# FPGA_board_and_power.net
KiCad netlist of a schematic drawn in Altium Designer
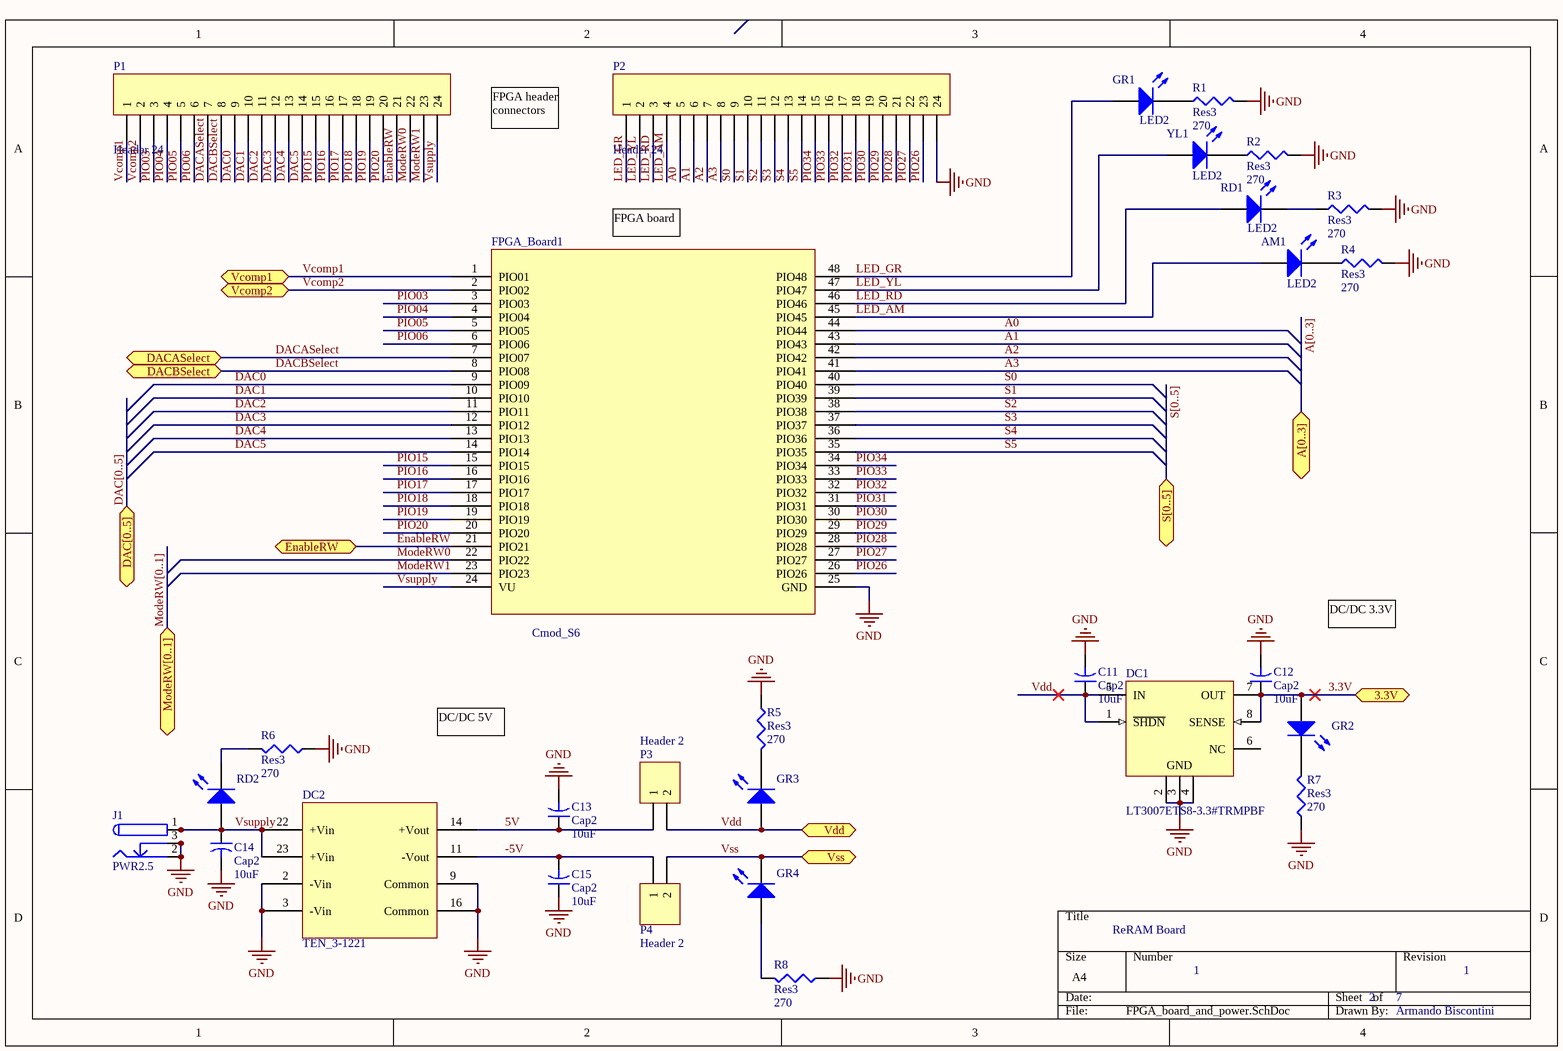
[diagram p0: FPGA_board_and_power.SchDoc]

(export (version "E")
  (design (tool "Eeschema 10.0.6"))
  (components
    (comp (ref "AM1")
      (value "LED2")
      (footprint "3.2X1.6X1.1")
      (description "Typical RED, GREEN, YELLOW, AMBER GaAs LED")
      (fields (field (name "PUBLISHER") "Altium Limited"))
      (libsource (lib "Miscellaneous Devices") (part "LED2"))
    )
    (comp (ref "C11")
      (value "Cap2")
      (footprint "CAPR5-4X5")
      (description "Capacitor")
      (fields (field (name "ALTIUM_VALUE") "10uF") (field (name "PUBLISHER") "Altium Limited"))
      (libsource (lib "Miscellaneous Devices") (part "Cap2"))
    )
    (comp (ref "C12")
      (value "Cap2")
      (footprint "CAPR5-4X5")
      (description "Capacitor")
      (fields (field (name "ALTIUM_VALUE") "10uF") (field (name "PUBLISHER") "Altium Limited"))
      (libsource (lib "Miscellaneous Devices") (part "Cap2"))
    )
    (comp (ref "C13")
      (value "Cap2")
      (footprint "CAPR5-4X5")
      (description "Capacitor")
      (fields (field (name "ALTIUM_VALUE") "10uF") (field (name "PUBLISHER") "Altium Limited"))
      (libsource (lib "Miscellaneous Devices") (part "Cap2"))
    )
    (comp (ref "C14")
      (value "Cap2")
      (footprint "CAPR5-4X5")
      (description "Capacitor")
      (fields (field (name "ALTIUM_VALUE") "10uF") (field (name "PUBLISHER") "Altium Limited"))
      (libsource (lib "Miscellaneous Devices") (part "Cap2"))
    )
    (comp (ref "C15")
      (value "Cap2")
      (footprint "CAPR5-4X5")
      (description "Capacitor")
      (fields (field (name "ALTIUM_VALUE") "10uF") (field (name "PUBLISHER") "Altium Limited"))
      (libsource (lib "Miscellaneous Devices") (part "Cap2"))
    )
    (comp (ref "DC1")
      (value "LT3007ETS8-3.3#TRMPBF")
      (footprint "LT-TS8-8-TSOT-23_V")
      (fields (field (name "MANUFACTURER") "Linear Technology"))
      (libsource (lib "Linear Technology Power Management LDO Linear Regulators") (part "LT3007ETS8-3.3#TRMPBF"))
    )
    (comp (ref "DC2")
      (value "TEN_3-1221")
      (footprint "TEN_3-1221")
      (description "Tracopower TEN 3-1221")
      (libsource (lib "ReRAM_Board_library") (part "TEN_3-1221"))
    )
    (comp (ref "FPGA_Board1")
      (value "Cmod_S6")
      (footprint "Cmod_S6_double_conn")
      (description "Digilent Cmod S6 Board")
      (libsource (lib "ReRAM_Board_library") (part "Cmod_S6"))
    )
    (comp (ref "GR1")
      (value "LED2")
      (footprint "3.2X1.6X1.1")
      (description "Typical RED, GREEN, YELLOW, AMBER GaAs LED")
      (fields (field (name "PUBLISHER") "Altium Limited"))
      (libsource (lib "Miscellaneous Devices") (part "LED2"))
    )
    (comp (ref "GR2")
      (value "~")
      (footprint "3.2X1.6X1.1")
      (description "Typical RED, GREEN, YELLOW, AMBER GaAs LED")
      (fields (field (name "PUBLISHER") "Altium Limited"))
      (libsource (lib "Miscellaneous Devices") (part "LED2"))
    )
    (comp (ref "GR3")
      (value "~")
      (footprint "3.2X1.6X1.1")
      (description "Typical RED, GREEN, YELLOW, AMBER GaAs LED")
      (fields (field (name "PUBLISHER") "Altium Limited"))
      (libsource (lib "Miscellaneous Devices") (part "LED2"))
    )
    (comp (ref "GR4")
      (value "~")
      (footprint "3.2X1.6X1.1")
      (description "Typical RED, GREEN, YELLOW, AMBER GaAs LED")
      (fields (field (name "PUBLISHER") "Altium Limited"))
      (libsource (lib "Miscellaneous Devices") (part "LED2"))
    )
    (comp (ref "J1")
      (value "PWR2.5")
      (footprint "KLD-0202")
      (description "Low Voltage Power Supply Connector")
      (fields (field (name "PUBLISHER") "Altium Limited"))
      (libsource (lib "Miscellaneous Connectors") (part "PWR2.5"))
    )
    (comp (ref "P1")
      (value "Header 24")
      (footprint "HDR1X24")
      (description "Header, 24-Pin")
      (fields (field (name "PUBLISHER") "Altium Limited"))
      (libsource (lib "Miscellaneous Connectors") (part "Header 24"))
    )
    (comp (ref "P2")
      (value "Header 24")
      (footprint "HDR1X24")
      (description "Header, 24-Pin")
      (fields (field (name "PUBLISHER") "Altium Limited"))
      (libsource (lib "Miscellaneous Connectors") (part "Header 24"))
    )
    (comp (ref "P3")
      (value "Header 2")
      (footprint "HDR1X2")
      (description "Header, 2-Pin")
      (fields (field (name "PUBLISHER") "Altium Limited"))
      (libsource (lib "") (part "Header 2_1"))
    )
    (comp (ref "P4")
      (value "Header 2")
      (footprint "HDR1X2")
      (description "Header, 2-Pin")
      (fields (field (name "PUBLISHER") "Altium Limited"))
      (libsource (lib "Miscellaneous Connectors") (part "Header 2"))
    )
    (comp (ref "R1")
      (value "Res3")
      (footprint "J1-0603")
      (description "Resistor")
      (fields (field (name "ALTIUM_VALUE") "270") (field (name "PUBLISHER") "Altium Limited"))
      (libsource (lib "Miscellaneous Devices") (part "Res3"))
    )
    (comp (ref "R2")
      (value "Res3")
      (footprint "J1-0603")
      (description "Resistor")
      (fields (field (name "ALTIUM_VALUE") "270") (field (name "PUBLISHER") "Altium Limited"))
      (libsource (lib "Miscellaneous Devices") (part "Res3"))
    )
    (comp (ref "R3")
      (value "Res3")
      (footprint "J1-0603")
      (description "Resistor")
      (fields (field (name "ALTIUM_VALUE") "270") (field (name "PUBLISHER") "Altium Limited"))
      (libsource (lib "Miscellaneous Devices") (part "Res3"))
    )
    (comp (ref "R4")
      (value "Res3")
      (footprint "J1-0603")
      (description "Resistor")
      (fields (field (name "ALTIUM_VALUE") "270") (field (name "PUBLISHER") "Altium Limited"))
      (libsource (lib "Miscellaneous Devices") (part "Res3"))
    )
    (comp (ref "R5")
      (value "Res3")
      (footprint "J1-0603")
      (description "Resistor")
      (fields (field (name "ALTIUM_VALUE") "270") (field (name "PUBLISHER") "Altium Limited"))
      (libsource (lib "Miscellaneous Devices") (part "Res3"))
    )
    (comp (ref "R6")
      (value "Res3")
      (footprint "J1-0603")
      (description "Resistor")
      (fields (field (name "ALTIUM_VALUE") "270") (field (name "PUBLISHER") "Altium Limited"))
      (libsource (lib "Miscellaneous Devices") (part "Res3"))
    )
    (comp (ref "R7")
      (value "Res3")
      (footprint "J1-0603")
      (description "Resistor")
      (fields (field (name "ALTIUM_VALUE") "270") (field (name "PUBLISHER") "Altium Limited"))
      (libsource (lib "Miscellaneous Devices") (part "Res3"))
    )
    (comp (ref "R8")
      (value "Res3")
      (footprint "J1-0603")
      (description "Resistor")
      (fields (field (name "ALTIUM_VALUE") "270") (field (name "PUBLISHER") "Altium Limited"))
      (libsource (lib "Miscellaneous Devices") (part "Res3"))
    )
    (comp (ref "RD1")
      (value "LED2")
      (footprint "3.2X1.6X1.1")
      (description "Typical RED, GREEN, YELLOW, AMBER GaAs LED")
      (fields (field (name "PUBLISHER") "Altium Limited"))
      (libsource (lib "Miscellaneous Devices") (part "LED2"))
    )
    (comp (ref "RD2")
      (value "~")
      (footprint "3.2X1.6X1.1")
      (description "Typical RED, GREEN, YELLOW, AMBER GaAs LED")
      (fields (field (name "PUBLISHER") "Altium Limited"))
      (libsource (lib "Miscellaneous Devices") (part "LED2"))
    )
    (comp (ref "YL1")
      (value "LED2")
      (footprint "3.2X1.6X1.1")
      (description "Typical RED, GREEN, YELLOW, AMBER GaAs LED")
      (fields (field (name "PUBLISHER") "Altium Limited"))
      (libsource (lib "Miscellaneous Devices") (part "LED2"))
    )
  )
  (nets
    (net (code "1") (name "/-5V") (class "Default")
      (node (ref "C15") (pin "2") (pinfunction "2_2") (pintype "passive"))
      (node (ref "DC2") (pin "11") (pinfunction "-Vout_11") (pintype "passive"))
      (node (ref "P4") (pin "1") (pinfunction "1_1") (pintype "passive"))
    )
    (net (code "2") (name "/3.3V") (class "Default")
      (node (ref "C12") (pin "1") (pinfunction "1_1") (pintype "passive"))
      (node (ref "DC1") (pin "7") (pinfunction "OUT_7") (pintype "power_in"))
      (node (ref "DC1") (pin "8") (pinfunction "SENSE_8") (pintype "input"))
      (node (ref "GR2") (pin "1") (pinfunction "A_1") (pintype "passive"))
    )
    (net (code "3") (name "/5V") (class "Default")
      (node (ref "C13") (pin "1") (pinfunction "1_1") (pintype "passive"))
      (node (ref "DC2") (pin "14") (pinfunction "+Vout_14") (pintype "passive"))
      (node (ref "P3") (pin "1") (pinfunction "1_1") (pintype "passive"))
    )
    (net (code "4") (name "/A0") (class "Default")
      (node (ref "FPGA_Board1") (pin "44") (pinfunction "PIO44_44") (pintype "passive"))
      (node (ref "P2") (pin "5") (pinfunction "5_5") (pintype "passive"))
    )
    (net (code "5") (name "/A1") (class "Default")
      (node (ref "FPGA_Board1") (pin "43") (pinfunction "PIO43_43") (pintype "passive"))
      (node (ref "P2") (pin "6") (pinfunction "6_6") (pintype "passive"))
    )
    (net (code "6") (name "/A2") (class "Default")
      (node (ref "FPGA_Board1") (pin "42") (pinfunction "PIO42_42") (pintype "passive"))
      (node (ref "P2") (pin "7") (pinfunction "7_7") (pintype "passive"))
    )
    (net (code "7") (name "/A3") (class "Default")
      (node (ref "FPGA_Board1") (pin "41") (pinfunction "PIO41_41") (pintype "passive"))
      (node (ref "P2") (pin "8") (pinfunction "8_8") (pintype "passive"))
    )
    (net (code "9") (name "/DAC0") (class "Default")
      (node (ref "FPGA_Board1") (pin "9") (pinfunction "PIO09_9") (pintype "passive"))
      (node (ref "P1") (pin "9") (pinfunction "9_9") (pintype "passive"))
    )
    (net (code "10") (name "/DAC1") (class "Default")
      (node (ref "FPGA_Board1") (pin "10") (pinfunction "PIO10_10") (pintype "passive"))
      (node (ref "P1") (pin "10") (pinfunction "10_10") (pintype "passive"))
    )
    (net (code "11") (name "/DAC2") (class "Default")
      (node (ref "FPGA_Board1") (pin "11") (pinfunction "PIO11_11") (pintype "passive"))
      (node (ref "P1") (pin "11") (pinfunction "11_11") (pintype "passive"))
    )
    (net (code "12") (name "/DAC3") (class "Default")
      (node (ref "FPGA_Board1") (pin "12") (pinfunction "PIO12_12") (pintype "passive"))
      (node (ref "P1") (pin "12") (pinfunction "12_12") (pintype "passive"))
    )
    (net (code "13") (name "/DAC4") (class "Default")
      (node (ref "FPGA_Board1") (pin "13") (pinfunction "PIO13_13") (pintype "passive"))
      (node (ref "P1") (pin "13") (pinfunction "13_13") (pintype "passive"))
    )
    (net (code "14") (name "/DAC5") (class "Default")
      (node (ref "FPGA_Board1") (pin "14") (pinfunction "PIO14_14") (pintype "passive"))
      (node (ref "P1") (pin "14") (pinfunction "14_14") (pintype "passive"))
    )
    (net (code "15") (name "/DACASelect") (class "Default")
      (node (ref "FPGA_Board1") (pin "7") (pinfunction "PIO07_7") (pintype "passive"))
      (node (ref "P1") (pin "7") (pinfunction "7_7") (pintype "passive"))
    )
    (net (code "16") (name "/DACBSelect") (class "Default")
      (node (ref "FPGA_Board1") (pin "8") (pinfunction "PIO08_8") (pintype "passive"))
      (node (ref "P1") (pin "8") (pinfunction "8_8") (pintype "passive"))
    )
    (net (code "18") (name "/EnableRW") (class "Default")
      (node (ref "FPGA_Board1") (pin "21") (pinfunction "PIO21_21") (pintype "passive"))
      (node (ref "P1") (pin "21") (pinfunction "21_21") (pintype "passive"))
    )
    (net (code "19") (name "/LED_AM") (class "Default")
      (node (ref "AM1") (pin "1") (pinfunction "A_1") (pintype "passive"))
      (node (ref "FPGA_Board1") (pin "45") (pinfunction "PIO45_45") (pintype "passive"))
      (node (ref "P2") (pin "4") (pinfunction "4_4") (pintype "passive"))
    )
    (net (code "20") (name "/LED_GR") (class "Default")
      (node (ref "FPGA_Board1") (pin "48") (pinfunction "PIO48_48") (pintype "passive"))
      (node (ref "GR1") (pin "1") (pinfunction "A_1") (pintype "passive"))
      (node (ref "P2") (pin "1") (pinfunction "1_1") (pintype "passive"))
    )
    (net (code "21") (name "/LED_RD") (class "Default")
      (node (ref "FPGA_Board1") (pin "46") (pinfunction "PIO46_46") (pintype "passive"))
      (node (ref "P2") (pin "3") (pinfunction "3_3") (pintype "passive"))
      (node (ref "RD1") (pin "1") (pinfunction "A_1") (pintype "passive"))
    )
    (net (code "22") (name "/LED_YL") (class "Default")
      (node (ref "FPGA_Board1") (pin "47") (pinfunction "PIO47_47") (pintype "passive"))
      (node (ref "P2") (pin "2") (pinfunction "2_2") (pintype "passive"))
      (node (ref "YL1") (pin "1") (pinfunction "A_1") (pintype "passive"))
    )
    (net (code "23") (name "/ModeRW0") (class "Default")
      (node (ref "FPGA_Board1") (pin "22") (pinfunction "PIO22_22") (pintype "passive"))
      (node (ref "P1") (pin "22") (pinfunction "22_22") (pintype "passive"))
    )
    (net (code "24") (name "/ModeRW1") (class "Default")
      (node (ref "FPGA_Board1") (pin "23") (pinfunction "PIO23_23") (pintype "passive"))
      (node (ref "P1") (pin "23") (pinfunction "23_23") (pintype "passive"))
    )
    (net (code "26") (name "/PIO03") (class "Default")
      (node (ref "FPGA_Board1") (pin "3") (pinfunction "PIO03_3") (pintype "passive"))
      (node (ref "P1") (pin "3") (pinfunction "3_3") (pintype "passive"))
    )
    (net (code "27") (name "/PIO04") (class "Default")
      (node (ref "FPGA_Board1") (pin "4") (pinfunction "PIO04_4") (pintype "passive"))
      (node (ref "P1") (pin "4") (pinfunction "4_4") (pintype "passive"))
    )
    (net (code "28") (name "/PIO05") (class "Default")
      (node (ref "FPGA_Board1") (pin "5") (pinfunction "PIO05_5") (pintype "passive"))
      (node (ref "P1") (pin "5") (pinfunction "5_5") (pintype "passive"))
    )
    (net (code "29") (name "/PIO06") (class "Default")
      (node (ref "FPGA_Board1") (pin "6") (pinfunction "PIO06_6") (pintype "passive"))
      (node (ref "P1") (pin "6") (pinfunction "6_6") (pintype "passive"))
    )
    (net (code "30") (name "/PIO15") (class "Default")
      (node (ref "FPGA_Board1") (pin "15") (pinfunction "PIO15_15") (pintype "passive"))
      (node (ref "P1") (pin "15") (pinfunction "15_15") (pintype "passive"))
    )
    (net (code "31") (name "/PIO16") (class "Default")
      (node (ref "FPGA_Board1") (pin "16") (pinfunction "PIO16_16") (pintype "passive"))
      (node (ref "P1") (pin "16") (pinfunction "16_16") (pintype "passive"))
    )
    (net (code "32") (name "/PIO17") (class "Default")
      (node (ref "FPGA_Board1") (pin "17") (pinfunction "PIO17_17") (pintype "passive"))
      (node (ref "P1") (pin "17") (pinfunction "17_17") (pintype "passive"))
    )
    (net (code "33") (name "/PIO18") (class "Default")
      (node (ref "FPGA_Board1") (pin "18") (pinfunction "PIO18_18") (pintype "passive"))
      (node (ref "P1") (pin "18") (pinfunction "18_18") (pintype "passive"))
    )
    (net (code "34") (name "/PIO19") (class "Default")
      (node (ref "FPGA_Board1") (pin "19") (pinfunction "PIO19_19") (pintype "passive"))
      (node (ref "P1") (pin "19") (pinfunction "19_19") (pintype "passive"))
    )
    (net (code "35") (name "/PIO20") (class "Default")
      (node (ref "FPGA_Board1") (pin "20") (pinfunction "PIO20_20") (pintype "passive"))
      (node (ref "P1") (pin "20") (pinfunction "20_20") (pintype "passive"))
    )
    (net (code "36") (name "/PIO26") (class "Default")
      (node (ref "FPGA_Board1") (pin "26") (pinfunction "PIO26_26") (pintype "passive"))
      (node (ref "P2") (pin "23") (pinfunction "23_23") (pintype "passive"))
    )
    (net (code "37") (name "/PIO27") (class "Default")
      (node (ref "FPGA_Board1") (pin "27") (pinfunction "PIO27_27") (pintype "passive"))
      (node (ref "P2") (pin "22") (pinfunction "22_22") (pintype "passive"))
    )
    (net (code "38") (name "/PIO28") (class "Default")
      (node (ref "FPGA_Board1") (pin "28") (pinfunction "PIO28_28") (pintype "passive"))
      (node (ref "P2") (pin "21") (pinfunction "21_21") (pintype "passive"))
    )
    (net (code "39") (name "/PIO29") (class "Default")
      (node (ref "FPGA_Board1") (pin "29") (pinfunction "PIO29_29") (pintype "passive"))
      (node (ref "P2") (pin "20") (pinfunction "20_20") (pintype "passive"))
    )
    (net (code "40") (name "/PIO30") (class "Default")
      (node (ref "FPGA_Board1") (pin "30") (pinfunction "PIO30_30") (pintype "passive"))
      (node (ref "P2") (pin "19") (pinfunction "19_19") (pintype "passive"))
    )
    (net (code "41") (name "/PIO31") (class "Default")
      (node (ref "FPGA_Board1") (pin "31") (pinfunction "PIO31_31") (pintype "passive"))
      (node (ref "P2") (pin "18") (pinfunction "18_18") (pintype "passive"))
    )
    (net (code "42") (name "/PIO32") (class "Default")
      (node (ref "FPGA_Board1") (pin "32") (pinfunction "PIO32_32") (pintype "passive"))
      (node (ref "P2") (pin "17") (pinfunction "17_17") (pintype "passive"))
    )
    (net (code "43") (name "/PIO33") (class "Default")
      (node (ref "FPGA_Board1") (pin "33") (pinfunction "PIO33_33") (pintype "passive"))
      (node (ref "P2") (pin "16") (pinfunction "16_16") (pintype "passive"))
    )
    (net (code "44") (name "/PIO34") (class "Default")
      (node (ref "FPGA_Board1") (pin "34") (pinfunction "PIO34_34") (pintype "passive"))
      (node (ref "P2") (pin "15") (pinfunction "15_15") (pintype "passive"))
    )
    (net (code "45") (name "/S0") (class "Default")
      (node (ref "FPGA_Board1") (pin "40") (pinfunction "PIO40_40") (pintype "passive"))
      (node (ref "P2") (pin "9") (pinfunction "9_9") (pintype "passive"))
    )
    (net (code "46") (name "/S1") (class "Default")
      (node (ref "FPGA_Board1") (pin "39") (pinfunction "PIO39_39") (pintype "passive"))
      (node (ref "P2") (pin "10") (pinfunction "10_10") (pintype "passive"))
    )
    (net (code "47") (name "/S2") (class "Default")
      (node (ref "FPGA_Board1") (pin "38") (pinfunction "PIO38_38") (pintype "passive"))
      (node (ref "P2") (pin "11") (pinfunction "11_11") (pintype "passive"))
    )
    (net (code "48") (name "/S3") (class "Default")
      (node (ref "FPGA_Board1") (pin "37") (pinfunction "PIO37_37") (pintype "passive"))
      (node (ref "P2") (pin "12") (pinfunction "12_12") (pintype "passive"))
    )
    (net (code "49") (name "/S4") (class "Default")
      (node (ref "FPGA_Board1") (pin "36") (pinfunction "PIO36_36") (pintype "passive"))
      (node (ref "P2") (pin "13") (pinfunction "13_13") (pintype "passive"))
    )
    (net (code "50") (name "/S5") (class "Default")
      (node (ref "FPGA_Board1") (pin "35") (pinfunction "PIO35_35") (pintype "passive"))
      (node (ref "P2") (pin "14") (pinfunction "14_14") (pintype "passive"))
    )
    (net (code "52") (name "/Vcomp1") (class "Default")
      (node (ref "FPGA_Board1") (pin "1") (pinfunction "PIO01_1") (pintype "passive"))
      (node (ref "P1") (pin "1") (pinfunction "1_1") (pintype "passive"))
    )
    (net (code "53") (name "/Vcomp2") (class "Default")
      (node (ref "FPGA_Board1") (pin "2") (pinfunction "PIO02_2") (pintype "passive"))
      (node (ref "P1") (pin "2") (pinfunction "2_2") (pintype "passive"))
    )
    (net (code "54") (name "/Vdd") (class "Default")
      (node (ref "C11") (pin "1") (pinfunction "1_1") (pintype "passive"))
      (node (ref "DC1") (pin "1") (pinfunction "~{SHDN}_1") (pintype "input"))
      (node (ref "DC1") (pin "5") (pinfunction "IN_5") (pintype "power_in"))
      (node (ref "GR3") (pin "1") (pinfunction "A_1") (pintype "passive"))
      (node (ref "P3") (pin "2") (pinfunction "2_2") (pintype "passive"))
    )
    (net (code "55") (name "/Vss") (class "Default")
      (node (ref "GR4") (pin "2") (pinfunction "K_2") (pintype "passive"))
      (node (ref "P4") (pin "2") (pinfunction "2_2") (pintype "passive"))
    )
    (net (code "56") (name "/Vsupply") (class "Default")
      (node (ref "C14") (pin "1") (pinfunction "1_1") (pintype "passive"))
      (node (ref "DC2") (pin "22") (pinfunction "+Vin_22") (pintype "passive"))
      (node (ref "DC2") (pin "23") (pinfunction "+Vin_23") (pintype "passive"))
      (node (ref "FPGA_Board1") (pin "24") (pinfunction "VU_24") (pintype "passive"))
      (node (ref "J1") (pin "1") (pinfunction "1_1") (pintype "power_in"))
      (node (ref "J1") (pin "1A") (pinfunction "1A_1A") (pintype "power_in"))
      (node (ref "J1") (pin "1B") (pinfunction "1B_1B") (pintype "power_in"))
      (node (ref "P1") (pin "24") (pinfunction "24_24") (pintype "passive"))
      (node (ref "RD2") (pin "1") (pinfunction "A_1") (pintype "passive"))
    )
    (net (code "57") (name "GND") (class "Default")
      (node (ref "C11") (pin "2") (pinfunction "2_2") (pintype "passive"))
      (node (ref "C12") (pin "2") (pinfunction "2_2") (pintype "passive"))
      (node (ref "C13") (pin "2") (pinfunction "2_2") (pintype "passive"))
      (node (ref "C14") (pin "2") (pinfunction "2_2") (pintype "passive"))
      (node (ref "C15") (pin "1") (pinfunction "1_1") (pintype "passive"))
      (node (ref "DC1") (pin "2") (pinfunction "GND_2") (pintype "power_in"))
      (node (ref "DC1") (pin "3") (pinfunction "GND_3") (pintype "power_in"))
      (node (ref "DC1") (pin "4") (pinfunction "GND_4") (pintype "power_in"))
      (node (ref "DC2") (pin "16") (pinfunction "Common_16") (pintype "passive"))
      (node (ref "DC2") (pin "2") (pinfunction "-Vin_2") (pintype "passive"))
      (node (ref "DC2") (pin "3") (pinfunction "-Vin_3") (pintype "passive"))
      (node (ref "DC2") (pin "9") (pinfunction "Common_9") (pintype "passive"))
      (node (ref "FPGA_Board1") (pin "25") (pinfunction "GND_25") (pintype "passive"))
      (node (ref "J1") (pin "2") (pinfunction "2_2") (pintype "power_in"))
      (node (ref "J1") (pin "2A") (pinfunction "2A_2A") (pintype "power_in"))
      (node (ref "J1") (pin "2B") (pinfunction "2B_2B") (pintype "power_in"))
      (node (ref "J1") (pin "3") (pinfunction "3_3") (pintype "power_in"))
      (node (ref "J1") (pin "3A") (pinfunction "3A_3A") (pintype "power_in"))
      (node (ref "J1") (pin "3B") (pinfunction "3B_3B") (pintype "power_in"))
      (node (ref "P2") (pin "24") (pinfunction "24_24") (pintype "passive"))
      (node (ref "R1") (pin "1") (pinfunction "1_1") (pintype "passive"))
      (node (ref "R2") (pin "1") (pinfunction "1_1") (pintype "passive"))
      (node (ref "R3") (pin "1") (pinfunction "1_1") (pintype "passive"))
      (node (ref "R4") (pin "1") (pinfunction "1_1") (pintype "passive"))
      (node (ref "R5") (pin "2") (pinfunction "2_2") (pintype "passive"))
      (node (ref "R6") (pin "2") (pinfunction "2_2") (pintype "passive"))
      (node (ref "R7") (pin "2") (pinfunction "2_2") (pintype "passive"))
      (node (ref "R8") (pin "2") (pinfunction "2_2") (pintype "passive"))
    )
    (net (code "58") (name "Net-(AM1-K)") (class "Default")
      (node (ref "AM1") (pin "2") (pinfunction "K_2") (pintype "passive"))
      (node (ref "R4") (pin "2") (pinfunction "2_2") (pintype "passive"))
    )
    (net (code "59") (name "Net-(GR1-K)") (class "Default")
      (node (ref "GR1") (pin "2") (pinfunction "K_2") (pintype "passive"))
      (node (ref "R1") (pin "2") (pinfunction "2_2") (pintype "passive"))
    )
    (net (code "60") (name "Net-(GR2-K)") (class "Default")
      (node (ref "GR2") (pin "2") (pinfunction "K_2") (pintype "passive"))
      (node (ref "R7") (pin "1") (pinfunction "1_1") (pintype "passive"))
    )
    (net (code "61") (name "Net-(GR3-K)") (class "Default")
      (node (ref "GR3") (pin "2") (pinfunction "K_2") (pintype "passive"))
      (node (ref "R5") (pin "1") (pinfunction "1_1") (pintype "passive"))
    )
    (net (code "62") (name "Net-(GR4-A)") (class "Default")
      (node (ref "GR4") (pin "1") (pinfunction "A_1") (pintype "passive"))
      (node (ref "R8") (pin "1") (pinfunction "1_1") (pintype "passive"))
    )
    (net (code "63") (name "Net-(RD1-K)") (class "Default")
      (node (ref "R3") (pin "2") (pinfunction "2_2") (pintype "passive"))
      (node (ref "RD1") (pin "2") (pinfunction "K_2") (pintype "passive"))
    )
    (net (code "64") (name "Net-(RD2-K)") (class "Default")
      (node (ref "R6") (pin "1") (pinfunction "1_1") (pintype "passive"))
      (node (ref "RD2") (pin "2") (pinfunction "K_2") (pintype "passive"))
    )
    (net (code "65") (name "Net-(YL1-K)") (class "Default")
      (node (ref "R2") (pin "2") (pinfunction "2_2") (pintype "passive"))
      (node (ref "YL1") (pin "2") (pinfunction "K_2") (pintype "passive"))
    )
    (net (code "66") (name "unconnected-(DC1-NC-Pad6)") (class "Default")
      (node (ref "DC1") (pin "6") (pinfunction "NC_6") (pintype "passive"))
    )
  )
)
